# Fleet-Monitor-MCU.net
KiCad netlist of a schematic drawn in Altium Designer
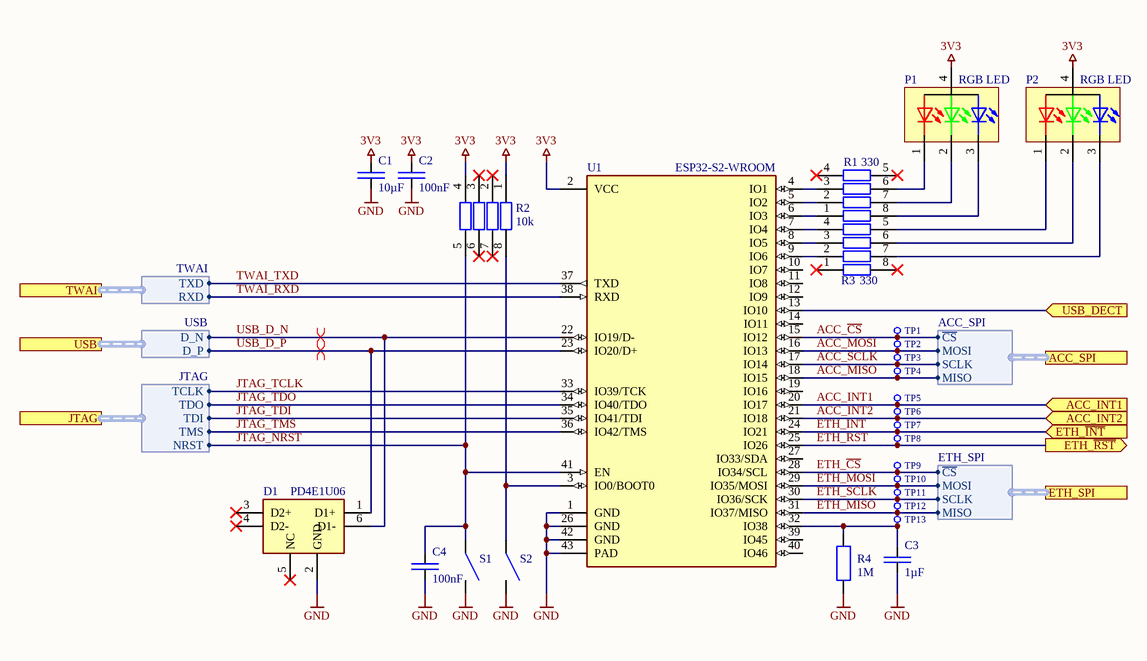
[diagram p0: Fleet-Monitor-MCU.SchDoc]

(export (version "E")
  (design (tool "Eeschema 10.0.6"))
  (components
    (comp (ref "C1")
      (value "10µF")
      (footprint "SMD Keramikkondensator 0603")
      (description "SMD Ceramic Capacitor E6")
      (libsource (lib "Ceramic Capacitors-E6") (part "E6 - 10uF"))
    )
    (comp (ref "C2")
      (value "100nF")
      (footprint "SMD Keramikkondensator 0603")
      (description "SMD Ceramic Capacitor E6")
      (libsource (lib "Ceramic Capacitors-E6") (part "E6 - 100nF"))
    )
    (comp (ref "C3")
      (value "1µF")
      (footprint "SMD Keramikkondensator 0603")
      (description "SMD Ceramic Capacitor E6")
      (libsource (lib "Fleet-Monitor") (part "E6 - 1uF"))
    )
    (comp (ref "C4")
      (value "100nF")
      (footprint "SMD Keramikkondensator 0603")
      (description "SMD Ceramic Capacitor E6")
      (libsource (lib "Ceramic Capacitors-E6") (part "E6 - 100nF"))
    )
    (comp (ref "D1")
      (value "PD4E1U06")
      (footprint "SMD IC SOT-363 (SC-70-6)")
      (description "Unidirectional 3A (8/20us) 15V (Typ) 6.5V 5.5V (Max) SOT-363 ESD Protection Devices ROHS")
      (libsource (lib "Fleet-Monitor") (part "PD4E1U06DCKR"))
    )
    (comp (ref "P1")
      (value "RGB LED")
      (footprint "SMD LED PLCC-4")
      (libsource (lib "Fleet-Monitor") (part "RGB LED"))
    )
    (comp (ref "P2")
      (value "RGB LED")
      (footprint "SMD LED PLCC-4")
      (libsource (lib "Fleet-Monitor") (part "RGB LED"))
    )
    (comp (ref "R1")
      (value "330")
      (footprint "SMD Widerstand Array 4-Fach 0603")
      (description "Isolated Resistor Array")
      (libsource (lib "Fleet-Monitor") (part "R-Array Single Quad E24 - 330"))
    )
    (comp (ref "R2")
      (value "10k")
      (footprint "SMD Widerstand Array 4-Fach 0603")
      (description "Isolated Resistor Array")
      (libsource (lib "Fleet-Monitor") (part "R-Array Single Quad E24 - 10k"))
    )
    (comp (ref "R3")
      (value "330")
      (footprint "SMD Widerstand Array 4-Fach 0603")
      (description "Isolated Resistor Array")
      (libsource (lib "Fleet-Monitor") (part "R-Array Single Quad E24 - 330"))
    )
    (comp (ref "R4")
      (value "1M")
      (footprint "SMD Widerstand 0603")
      (description "SMD Chip Resistor E24")
      (libsource (lib "Fleet-Monitor") (part "E96 - 1M"))
    )
    (comp (ref "S1")
      (value "SMD-Button")
      (footprint "SMD Button 5.2x5.2")
      (description "Button SPST")
      (libsource (lib "Switches") (part "Button 3mmx2.5mm"))
    )
    (comp (ref "S2")
      (value "SMD-Button")
      (footprint "SMD Button 5.2x5.2")
      (description "Button SPST")
      (libsource (lib "Switches") (part "Button 3mmx2.5mm"))
    )
    (comp (ref "TP1")
      (value "X-TP")
      (footprint "SMD Testpunkt Ø1mm")
      (description "Testpunkt")
      (libsource (lib "VLD-Monitor_V1.0") (part "X-TP"))
    )
    (comp (ref "TP2")
      (value "X-TP")
      (footprint "SMD Testpunkt Ø1mm")
      (description "Testpunkt")
      (libsource (lib "VLD-Monitor_V1.0") (part "X-TP"))
    )
    (comp (ref "TP3")
      (value "X-TP")
      (footprint "SMD Testpunkt Ø1mm")
      (description "Testpunkt")
      (libsource (lib "VLD-Monitor_V1.0") (part "X-TP"))
    )
    (comp (ref "TP4")
      (value "X-TP")
      (footprint "SMD Testpunkt Ø1mm")
      (description "Testpunkt")
      (libsource (lib "VLD-Monitor_V1.0") (part "X-TP"))
    )
    (comp (ref "TP5")
      (value "X-TP")
      (footprint "SMD Testpunkt Ø1mm")
      (description "Testpunkt")
      (libsource (lib "VLD-Monitor_V1.0") (part "X-TP"))
    )
    (comp (ref "TP6")
      (value "X-TP")
      (footprint "SMD Testpunkt Ø1mm")
      (description "Testpunkt")
      (libsource (lib "VLD-Monitor_V1.0") (part "X-TP"))
    )
    (comp (ref "TP7")
      (value "X-TP")
      (footprint "SMD Testpunkt Ø1mm")
      (description "Testpunkt")
      (libsource (lib "VLD-Monitor_V1.0") (part "X-TP"))
    )
    (comp (ref "TP8")
      (value "X-TP")
      (footprint "SMD Testpunkt Ø1mm")
      (description "Testpunkt")
      (libsource (lib "VLD-Monitor_V1.0") (part "X-TP"))
    )
    (comp (ref "TP9")
      (value "X-TP")
      (footprint "SMD Testpunkt Ø1mm")
      (description "Testpunkt")
      (libsource (lib "VLD-Monitor_V1.0") (part "X-TP"))
    )
    (comp (ref "TP10")
      (value "X-TP")
      (footprint "SMD Testpunkt Ø1mm")
      (description "Testpunkt")
      (libsource (lib "VLD-Monitor_V1.0") (part "X-TP"))
    )
    (comp (ref "TP11")
      (value "X-TP")
      (footprint "SMD Testpunkt Ø1mm")
      (description "Testpunkt")
      (libsource (lib "VLD-Monitor_V1.0") (part "X-TP"))
    )
    (comp (ref "TP12")
      (value "X-TP")
      (footprint "SMD Testpunkt Ø1mm")
      (description "Testpunkt")
      (libsource (lib "VLD-Monitor_V1.0") (part "X-TP"))
    )
    (comp (ref "TP13")
      (value "X-TP")
      (footprint "SMD Testpunkt Ø1mm")
      (description "Testpunkt")
      (libsource (lib "VLD-Monitor_V1.0") (part "X-TP"))
    )
    (comp (ref "U1")
      (value "ESP32-S2-WROOM")
      (footprint "SMD ESP32-S2-WROOM")
      (description "WiFi 802.11b/g/n Transceiver Module 2.4GHz Antenna, I-PEX Surface Mount")
      (libsource (lib "Fleet-Monitor") (part "ESP32-S2-WROOM"))
    )
  )
  (nets
    (net (code "6") (name "/ACC_INT1") (class "Default")
      (node (ref "TP5") (pin "1") (pinfunction "1_1") (pintype "passive"))
      (node (ref "U1") (pin "20") (pinfunction "IO17_20") (pintype "bidirectional"))
    )
    (net (code "7") (name "/ACC_INT2") (class "Default")
      (node (ref "TP6") (pin "1") (pinfunction "1_1") (pintype "passive"))
      (node (ref "U1") (pin "21") (pinfunction "IO18_21") (pintype "bidirectional"))
    )
    (net (code "8") (name "/ACC_MISO") (class "Default")
      (node (ref "TP4") (pin "1") (pinfunction "1_1") (pintype "passive"))
      (node (ref "U1") (pin "18") (pinfunction "IO15_18") (pintype "bidirectional"))
    )
    (net (code "9") (name "/ACC_MOSI") (class "Default")
      (node (ref "TP2") (pin "1") (pinfunction "1_1") (pintype "passive"))
      (node (ref "U1") (pin "16") (pinfunction "IO13_16") (pintype "bidirectional"))
    )
    (net (code "10") (name "/ACC_SCLK") (class "Default")
      (node (ref "TP3") (pin "1") (pinfunction "1_1") (pintype "passive"))
      (node (ref "U1") (pin "17") (pinfunction "IO14_17") (pintype "bidirectional"))
    )
    (net (code "11") (name "/ACC_~{CS}") (class "Default")
      (node (ref "TP1") (pin "1") (pinfunction "1_1") (pintype "passive"))
      (node (ref "U1") (pin "15") (pinfunction "IO12_15") (pintype "bidirectional"))
    )
    (net (code "12") (name "/ETH_MISO") (class "Default")
      (node (ref "TP12") (pin "1") (pinfunction "1_1") (pintype "passive"))
      (node (ref "U1") (pin "31") (pinfunction "IO37/MISO_31") (pintype "bidirectional"))
    )
    (net (code "13") (name "/ETH_MOSI") (class "Default")
      (node (ref "TP10") (pin "1") (pinfunction "1_1") (pintype "passive"))
      (node (ref "U1") (pin "29") (pinfunction "IO35/MOSI_29") (pintype "bidirectional"))
    )
    (net (code "14") (name "/ETH_SCLK") (class "Default")
      (node (ref "TP11") (pin "1") (pinfunction "1_1") (pintype "passive"))
      (node (ref "U1") (pin "30") (pinfunction "IO36/SCK_30") (pintype "bidirectional"))
    )
    (net (code "15") (name "/ETH_~{CS}") (class "Default")
      (node (ref "TP9") (pin "1") (pinfunction "1_1") (pintype "passive"))
      (node (ref "U1") (pin "28") (pinfunction "IO34/SCL_28") (pintype "bidirectional"))
    )
    (net (code "16") (name "/ETH_~{INT}") (class "Default")
      (node (ref "TP7") (pin "1") (pinfunction "1_1") (pintype "passive"))
      (node (ref "U1") (pin "24") (pinfunction "IO21_24") (pintype "bidirectional"))
    )
    (net (code "17") (name "/ETH_~{RST}") (class "Default")
      (node (ref "TP8") (pin "1") (pinfunction "1_1") (pintype "passive"))
      (node (ref "U1") (pin "25") (pinfunction "IO26_25") (pintype "bidirectional"))
    )
    (net (code "18") (name "/JTAG_NRST") (class "Default")
      (node (ref "C4") (pin "2") (pinfunction "2_2") (pintype "passive"))
      (node (ref "R2") (pin "5") (pinfunction "5_5") (pintype "passive"))
      (node (ref "S1") (pin "1") (pinfunction "1_1") (pintype "passive"))
      (node (ref "U1") (pin "41") (pinfunction "EN_41") (pintype "input"))
    )
    (net (code "19") (name "/JTAG_TCLK") (class "Default")
      (node (ref "U1") (pin "33") (pinfunction "IO39/TCK_33") (pintype "bidirectional"))
    )
    (net (code "20") (name "/JTAG_TDI") (class "Default")
      (node (ref "U1") (pin "35") (pinfunction "IO41/TDI_35") (pintype "bidirectional"))
    )
    (net (code "21") (name "/JTAG_TDO") (class "Default")
      (node (ref "U1") (pin "34") (pinfunction "IO40/TDO_34") (pintype "bidirectional"))
    )
    (net (code "22") (name "/JTAG_TMS") (class "Default")
      (node (ref "U1") (pin "36") (pinfunction "IO42/TMS_36") (pintype "bidirectional"))
    )
    (net (code "23") (name "/TWAI_RXD") (class "Default")
      (node (ref "U1") (pin "38") (pinfunction "RXD_38") (pintype "input"))
    )
    (net (code "24") (name "/TWAI_TXD") (class "Default")
      (node (ref "U1") (pin "37") (pinfunction "TXD_37") (pintype "output"))
    )
    (net (code "25") (name "/USB_DECT") (class "Default")
      (node (ref "U1") (pin "13") (pinfunction "IO10_13") (pintype "bidirectional"))
    )
    (net (code "26") (name "/USB_D_N") (class "Default")
      (node (ref "D1") (pin "6") (pinfunction "D1-_6") (pintype "passive"))
      (node (ref "U1") (pin "22") (pinfunction "IO19/D-_22") (pintype "bidirectional"))
    )
    (net (code "27") (name "/USB_D_P") (class "Default")
      (node (ref "D1") (pin "1") (pinfunction "D1+_1") (pintype "passive"))
      (node (ref "U1") (pin "23") (pinfunction "IO20/D+_23") (pintype "bidirectional"))
    )
    (net (code "33") (name "3V3") (class "Default")
      (node (ref "C1") (pin "2") (pinfunction "2_2") (pintype "passive"))
      (node (ref "C2") (pin "2") (pinfunction "2_2") (pintype "passive"))
      (node (ref "P1") (pin "4") (pinfunction "4_4") (pintype "passive"))
      (node (ref "P2") (pin "4") (pinfunction "4_4") (pintype "passive"))
      (node (ref "R2") (pin "1") (pinfunction "1_1") (pintype "passive"))
      (node (ref "R2") (pin "4") (pinfunction "4_4") (pintype "passive"))
      (node (ref "U1") (pin "2") (pinfunction "VCC_2") (pintype "passive"))
    )
    (net (code "34") (name "GND") (class "Default")
      (node (ref "C1") (pin "1") (pinfunction "1_1") (pintype "passive"))
      (node (ref "C2") (pin "1") (pinfunction "1_1") (pintype "passive"))
      (node (ref "C3") (pin "1") (pinfunction "1_1") (pintype "passive"))
      (node (ref "C4") (pin "1") (pinfunction "1_1") (pintype "passive"))
      (node (ref "D1") (pin "2") (pinfunction "GND_2") (pintype "passive"))
      (node (ref "R4") (pin "2") (pinfunction "2_2") (pintype "passive"))
      (node (ref "S1") (pin "2") (pinfunction "2_2") (pintype "passive"))
      (node (ref "S2") (pin "2") (pinfunction "2_2") (pintype "passive"))
      (node (ref "U1") (pin "1") (pinfunction "GND_1") (pintype "passive"))
      (node (ref "U1") (pin "26") (pinfunction "GND_26") (pintype "passive"))
      (node (ref "U1") (pin "42") (pinfunction "GND_42") (pintype "passive"))
      (node (ref "U1") (pin "43") (pinfunction "PAD_43") (pintype "passive"))
    )
    (net (code "35") (name "Net-(P1-Pad1)") (class "Default")
      (node (ref "P1") (pin "1") (pinfunction "1_1") (pintype "passive"))
      (node (ref "R1") (pin "6") (pinfunction "6_6") (pintype "passive"))
    )
    (net (code "36") (name "Net-(P1-Pad2)") (class "Default")
      (node (ref "P1") (pin "2") (pinfunction "2_2") (pintype "passive"))
      (node (ref "R1") (pin "7") (pinfunction "7_7") (pintype "passive"))
    )
    (net (code "37") (name "Net-(P1-Pad3)") (class "Default")
      (node (ref "P1") (pin "3") (pinfunction "3_3") (pintype "passive"))
      (node (ref "R1") (pin "8") (pinfunction "8_8") (pintype "passive"))
    )
    (net (code "38") (name "Net-(P2-Pad1)") (class "Default")
      (node (ref "P2") (pin "1") (pinfunction "1_1") (pintype "passive"))
      (node (ref "R3") (pin "5") (pinfunction "5_5") (pintype "passive"))
    )
    (net (code "39") (name "Net-(P2-Pad2)") (class "Default")
      (node (ref "P2") (pin "2") (pinfunction "2_2") (pintype "passive"))
      (node (ref "R3") (pin "6") (pinfunction "6_6") (pintype "passive"))
    )
    (net (code "40") (name "Net-(P2-Pad3)") (class "Default")
      (node (ref "P2") (pin "3") (pinfunction "3_3") (pintype "passive"))
      (node (ref "R3") (pin "7") (pinfunction "7_7") (pintype "passive"))
    )
    (net (code "41") (name "Net-(U1-IO0{slash}BOOT0)") (class "Default")
      (node (ref "R2") (pin "8") (pinfunction "8_8") (pintype "passive"))
      (node (ref "S2") (pin "1") (pinfunction "1_1") (pintype "passive"))
      (node (ref "U1") (pin "3") (pinfunction "IO0/BOOT0_3") (pintype "bidirectional"))
    )
    (net (code "42") (name "Net-(U1-IO1)") (class "Default")
      (node (ref "R1") (pin "3") (pinfunction "3_3") (pintype "passive"))
      (node (ref "U1") (pin "4") (pinfunction "IO1_4") (pintype "bidirectional"))
    )
    (net (code "43") (name "Net-(U1-IO2)") (class "Default")
      (node (ref "R1") (pin "2") (pinfunction "2_2") (pintype "passive"))
      (node (ref "U1") (pin "5") (pinfunction "IO2_5") (pintype "bidirectional"))
    )
    (net (code "44") (name "Net-(U1-IO3)") (class "Default")
      (node (ref "R1") (pin "1") (pinfunction "1_1") (pintype "passive"))
      (node (ref "U1") (pin "6") (pinfunction "IO3_6") (pintype "bidirectional"))
    )
    (net (code "45") (name "Net-(U1-IO4)") (class "Default")
      (node (ref "R3") (pin "4") (pinfunction "4_4") (pintype "passive"))
      (node (ref "U1") (pin "7") (pinfunction "IO4_7") (pintype "bidirectional"))
    )
    (net (code "46") (name "Net-(U1-IO5)") (class "Default")
      (node (ref "R3") (pin "3") (pinfunction "3_3") (pintype "passive"))
      (node (ref "U1") (pin "8") (pinfunction "IO5_8") (pintype "bidirectional"))
    )
    (net (code "47") (name "Net-(U1-IO6)") (class "Default")
      (node (ref "R3") (pin "2") (pinfunction "2_2") (pintype "passive"))
      (node (ref "U1") (pin "9") (pinfunction "IO6_9") (pintype "bidirectional"))
    )
    (net (code "48") (name "Net-(U1-IO38)") (class "Default")
      (node (ref "C3") (pin "2") (pinfunction "2_2") (pintype "passive"))
      (node (ref "R4") (pin "1") (pinfunction "1_1") (pintype "passive"))
      (node (ref "TP13") (pin "1") (pinfunction "1_1") (pintype "passive"))
      (node (ref "U1") (pin "32") (pinfunction "IO38_32") (pintype "bidirectional"))
    )
    (net (code "49") (name "unconnected-(D1-D2+-Pad3)") (class "Default")
      (node (ref "D1") (pin "3") (pinfunction "D2+_3") (pintype "passive+no_connect"))
    )
    (net (code "50") (name "unconnected-(D1-D2--Pad4)") (class "Default")
      (node (ref "D1") (pin "4") (pinfunction "D2-_4") (pintype "passive+no_connect"))
    )
    (net (code "51") (name "unconnected-(D1-NC-Pad5)") (class "Default")
      (node (ref "D1") (pin "5") (pinfunction "NC_5") (pintype "passive+no_connect"))
    )
    (net (code "52") (name "unconnected-(R1-Pad4)") (class "Default")
      (node (ref "R1") (pin "4") (pinfunction "4_4") (pintype "passive+no_connect"))
    )
    (net (code "53") (name "unconnected-(R1-Pad5)") (class "Default")
      (node (ref "R1") (pin "5") (pinfunction "5_5") (pintype "passive+no_connect"))
    )
    (net (code "54") (name "unconnected-(R2-Pad2)") (class "Default")
      (node (ref "R2") (pin "2") (pinfunction "2_2") (pintype "passive+no_connect"))
    )
    (net (code "55") (name "unconnected-(R2-Pad3)") (class "Default")
      (node (ref "R2") (pin "3") (pinfunction "3_3") (pintype "passive+no_connect"))
    )
    (net (code "56") (name "unconnected-(R2-Pad6)") (class "Default")
      (node (ref "R2") (pin "6") (pinfunction "6_6") (pintype "passive+no_connect"))
    )
    (net (code "57") (name "unconnected-(R2-Pad7)") (class "Default")
      (node (ref "R2") (pin "7") (pinfunction "7_7") (pintype "passive+no_connect"))
    )
    (net (code "58") (name "unconnected-(R3-Pad1)") (class "Default")
      (node (ref "R3") (pin "1") (pinfunction "1_1") (pintype "passive+no_connect"))
    )
    (net (code "59") (name "unconnected-(R3-Pad8)") (class "Default")
      (node (ref "R3") (pin "8") (pinfunction "8_8") (pintype "passive+no_connect"))
    )
    (net (code "60") (name "unconnected-(U1-IO7-Pad10)") (class "Default")
      (node (ref "U1") (pin "10") (pinfunction "IO7_10") (pintype "bidirectional"))
    )
    (net (code "61") (name "unconnected-(U1-IO8-Pad11)") (class "Default")
      (node (ref "U1") (pin "11") (pinfunction "IO8_11") (pintype "bidirectional"))
    )
    (net (code "62") (name "unconnected-(U1-IO9-Pad12)") (class "Default")
      (node (ref "U1") (pin "12") (pinfunction "IO9_12") (pintype "bidirectional"))
    )
    (net (code "63") (name "unconnected-(U1-IO11-Pad14)") (class "Default")
      (node (ref "U1") (pin "14") (pinfunction "IO11_14") (pintype "bidirectional"))
    )
    (net (code "64") (name "unconnected-(U1-IO16-Pad19)") (class "Default")
      (node (ref "U1") (pin "19") (pinfunction "IO16_19") (pintype "bidirectional"))
    )
    (net (code "65") (name "unconnected-(U1-IO33{slash}SDA-Pad27)") (class "Default")
      (node (ref "U1") (pin "27") (pinfunction "IO33/SDA_27") (pintype "bidirectional"))
    )
    (net (code "66") (name "unconnected-(U1-IO45-Pad39)") (class "Default")
      (node (ref "U1") (pin "39") (pinfunction "IO45_39") (pintype "bidirectional"))
    )
    (net (code "67") (name "unconnected-(U1-IO46-Pad40)") (class "Default")
      (node (ref "U1") (pin "40") (pinfunction "IO46_40") (pintype "bidirectional"))
    )
  )
)
